# eco_Main_v1_0.net
KiCad netlist of a schematic drawn in Altium Designer
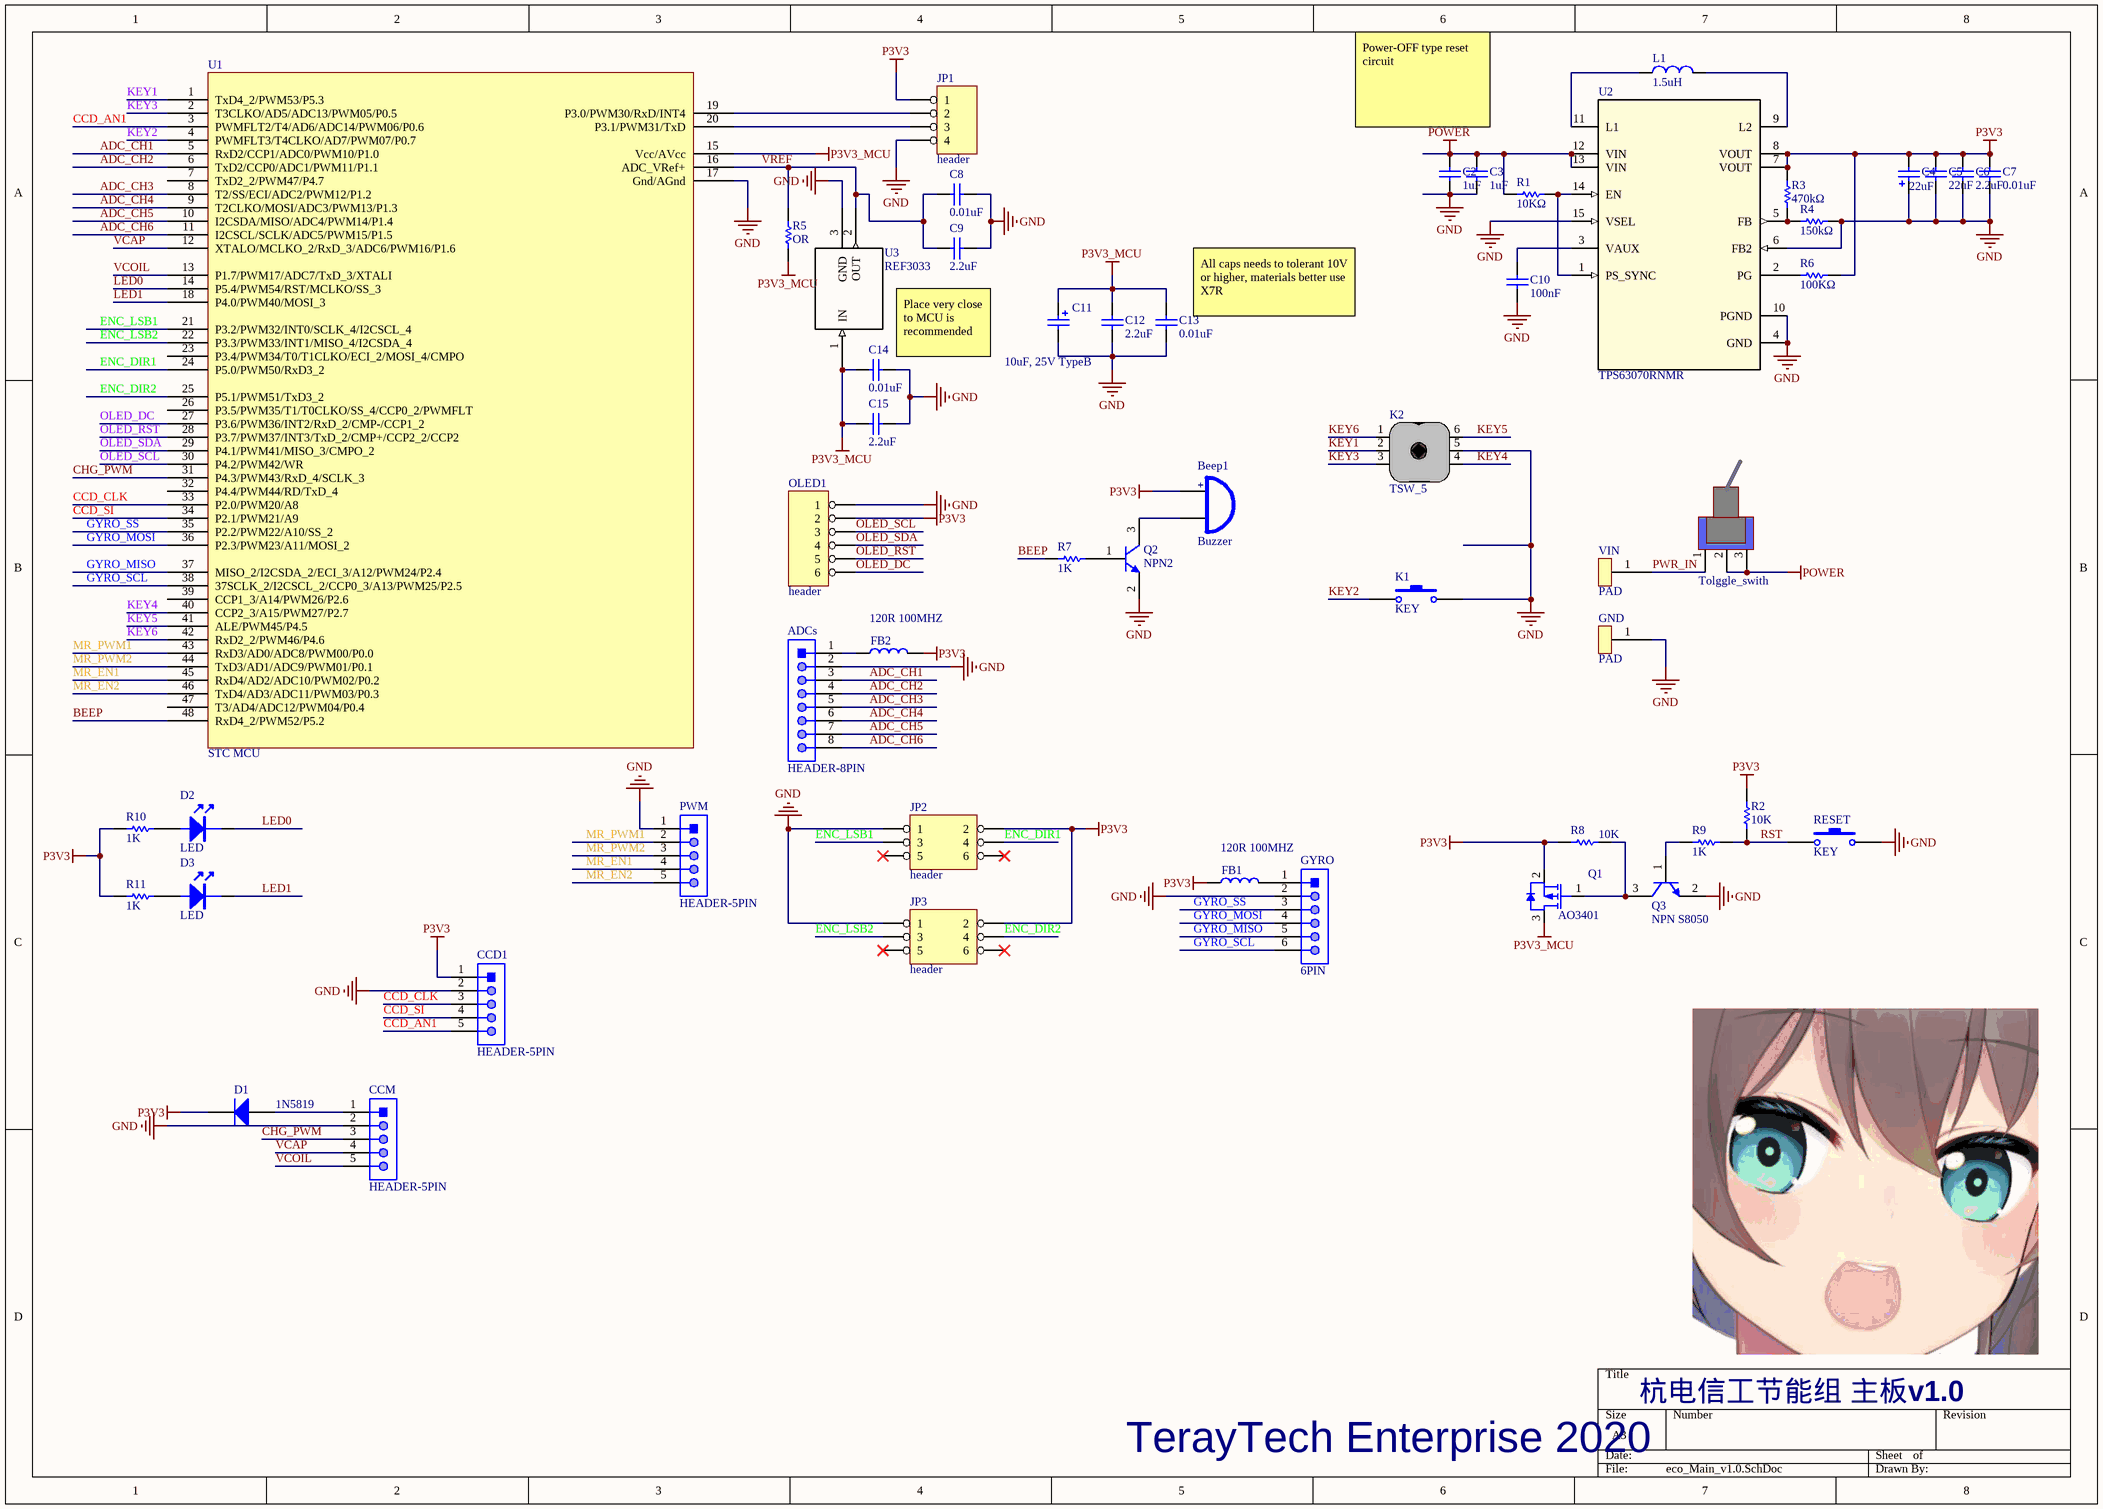
[diagram p0: eco_Main_v1.0.SchDoc]

(export (version "E")
  (design (tool "Eeschema 10.0.6"))
  (components
    (comp (ref "ADCs")
      (value "HEADER-8PIN")
      (footprint "HEADER_8P_1.25_RT")
      (libsource (lib "My Footprint") (part "HEADER-8PIN"))
    )
    (comp (ref "Beep1")
      (value "Buzzer")
      (footprint "BUZZER_9.6*9.6*5mm")
      (libsource (lib "My Footprint") (part "Buzzer"))
    )
    (comp (ref "C2")
      (value "1uF")
      (footprint "C1206")
      (description "Capacitor")
      (fields (field (name "PUBLISHER") "Altium Limited"))
      (libsource (lib "My Footprint") (part "CAP"))
    )
    (comp (ref "C3")
      (value "1uF")
      (footprint "0603_C")
      (description "Capacitor")
      (fields (field (name "PUBLISHER") "Altium Limited"))
      (libsource (lib "My Footprint") (part "CAP"))
    )
    (comp (ref "C4")
      (value "22uF")
      (footprint "CAPC3528B")
      (description "Capacitor")
      (fields (field (name "PUBLISHER") "Altium Limited"))
      (libsource (lib "My Footprint") (part "CAP_tan"))
    )
    (comp (ref "C5")
      (value "22uF")
      (footprint "C1206")
      (description "Capacitor")
      (fields (field (name "PUBLISHER") "Altium Limited"))
      (libsource (lib "My Footprint") (part "CAP"))
    )
    (comp (ref "C6")
      (value "2.2uF")
      (footprint "0603_C")
      (description "Capacitor")
      (fields (field (name "PUBLISHER") "Altium Limited"))
      (libsource (lib "My Footprint") (part "CAP"))
    )
    (comp (ref "C7")
      (value "0.01uF")
      (footprint "0603_C")
      (description "Capacitor")
      (fields (field (name "PUBLISHER") "Altium Limited"))
      (libsource (lib "My Footprint") (part "CAP"))
    )
    (comp (ref "C8")
      (value "0.01uF")
      (footprint "0603_C")
      (description "Capacitor")
      (fields (field (name "PUBLISHER") "Altium Limited"))
      (libsource (lib "My Footprint") (part "CAP"))
    )
    (comp (ref "C9")
      (value "2.2uF")
      (footprint "0603_C")
      (description "Capacitor")
      (fields (field (name "PUBLISHER") "Altium Limited"))
      (libsource (lib "My Footprint") (part "CAP"))
    )
    (comp (ref "C10")
      (value "100nF")
      (footprint "0603_C")
      (description "Capacitor")
      (fields (field (name "PUBLISHER") "Altium Limited"))
      (libsource (lib "My Footprint") (part "CAP"))
    )
    (comp (ref "C11")
      (value "10uF, 25V TypeB")
      (footprint "CAPC3528B")
      (description "Capacitor")
      (fields (field (name "PUBLISHER") "Altium Limited"))
      (libsource (lib "My Footprint") (part "CAP_tan"))
    )
    (comp (ref "C12")
      (value "2.2uF")
      (footprint "0603_C")
      (description "Capacitor")
      (fields (field (name "PUBLISHER") "Altium Limited"))
      (libsource (lib "My Footprint") (part "CAP"))
    )
    (comp (ref "C13")
      (value "0.01uF")
      (footprint "0603_C")
      (description "Capacitor")
      (fields (field (name "PUBLISHER") "Altium Limited"))
      (libsource (lib "My Footprint") (part "CAP"))
    )
    (comp (ref "C14")
      (value "0.01uF")
      (footprint "0603_C")
      (description "Capacitor")
      (fields (field (name "PUBLISHER") "Altium Limited"))
      (libsource (lib "My Footprint") (part "CAP"))
    )
    (comp (ref "C15")
      (value "2.2uF")
      (footprint "0603_C")
      (description "Capacitor")
      (fields (field (name "PUBLISHER") "Altium Limited"))
      (libsource (lib "My Footprint") (part "CAP"))
    )
    (comp (ref "CCD1")
      (value "HEADER-5PIN")
      (footprint "HEADER_5P_1.25_up")
      (libsource (lib "My Footprint") (part "HEADER-5PIN"))
    )
    (comp (ref "CCM")
      (value "HEADER-5PIN")
      (footprint "HEADER_5P_1.25_RT")
      (libsource (lib "My Footprint") (part "HEADER-5PIN"))
    )
    (comp (ref "D1")
      (value "1N5819")
      (footprint "SOD123")
      (description "40V 1A PEAK 25a")
      (libsource (lib "My Footprint") (part "1N5819"))
    )
    (comp (ref "D2")
      (value "LED")
      (footprint "0603_LED")
      (description "LED 发光二极管")
      (libsource (lib "My Footprint") (part "LED"))
    )
    (comp (ref "D3")
      (value "LED")
      (footprint "0603_LED")
      (description "LED 发光二极管")
      (libsource (lib "My Footprint") (part "LED"))
    )
    (comp (ref "Energy1")
      (value "Tolggle_swith")
      (footprint "TOGGLE SWICH STAND")
      (libsource (lib "SamacSys") (part "Tolggle_swith"))
    )
    (comp (ref "FB1")
      (value "120R 100MHZ")
      (footprint "FB0603")
      (description "120OHM@100MHZ 2A 25% 0603")
      (libsource (lib "My Footprint") (part "FB"))
    )
    (comp (ref "FB2")
      (value "120R 100MHZ")
      (footprint "FB0603")
      (description "120OHM@100MHZ 2A 25% 0603")
      (libsource (lib "My Footprint") (part "FB"))
    )
    (comp (ref "GND") (value "PAD") (footprint "PAD") (libsource (lib "My Footprint") (part "PAD")))
    (comp (ref "GYRO")
      (value "6PIN")
      (footprint "MX 1.25-WS-6P")
      (libsource (lib "My Footprint") (part "HEADER-6PIN"))
    )
    (comp (ref "JP1")
      (value "header")
      (footprint "header4")
      (libsource (lib "My Footprint") (part "HEADER 4"))
    )
    (comp (ref "JP2")
      (value "header")
      (footprint "header2X3")
      (libsource (lib "My Footprint") (part "HEADER 3X2"))
    )
    (comp (ref "JP3")
      (value "header")
      (footprint "header2X3")
      (libsource (lib "My Footprint") (part "HEADER 3X2"))
    )
    (comp (ref "K1")
      (value "KEY")
      (footprint "贴片复位开关")
      (description "Switch")
      (fields (field (name "PUBLISHER") "Altium Limited"))
      (libsource (lib "My Footprint") (part "KEY_2"))
    )
    (comp (ref "K2")
      (value "TSW_5")
      (footprint "TSW-10")
      (description "方向开关")
      (libsource (lib "My Footprint") (part "TSW_5"))
    )
    (comp (ref "L1") (value "1.5uH") (footprint "L 5x5") (libsource (lib "My Footprint") (part "Inductor")))
    (comp (ref "OLED1")
      (value "header")
      (footprint "0.96寸OLED模块")
      (libsource (lib "My Footprint") (part "HEADER 6"))
    )
    (comp (ref "PWM")
      (value "HEADER-5PIN")
      (footprint "HEADER_5P_1.25_RT")
      (libsource (lib "My Footprint") (part "HEADER-5PIN"))
    )
    (comp (ref "Q1")
      (value "AO3401")
      (footprint "SOT-23-3")
      (libsource (lib "SamacSys") (part "p-MOSEFT_SMALL"))
    )
    (comp (ref "Q2")
      (value "NPN2")
      (footprint "SOT-23-3")
      (description "贴片")
      (libsource (lib "My Footprint") (part "NPN2"))
    )
    (comp (ref "Q3")
      (value "NPN S8050")
      (footprint "SOT-23-3")
      (description "贴片")
      (libsource (lib "My Footprint") (part "NPN2"))
    )
    (comp (ref "R1")
      (value "10KΩ")
      (footprint "0603_R")
      (description "Resistor")
      (fields (field (name "PUBLISHER") "Altium Limited"))
      (libsource (lib "My Footprint") (part "RES0"))
    )
    (comp (ref "R2")
      (value "10K")
      (footprint "0603_R")
      (description "Resistor")
      (fields (field (name "PUBLISHER") "Altium Limited"))
      (libsource (lib "My Footprint") (part "RES0"))
    )
    (comp (ref "R3")
      (value "470kΩ")
      (footprint "0603_R")
      (description "Resistor")
      (fields (field (name "PUBLISHER") "Altium Limited"))
      (libsource (lib "My Footprint") (part "RES0"))
    )
    (comp (ref "R4")
      (value "150kΩ")
      (footprint "0603_R")
      (description "Resistor")
      (fields (field (name "PUBLISHER") "Altium Limited"))
      (libsource (lib "My Footprint") (part "RES0"))
    )
    (comp (ref "R5")
      (value "OR")
      (footprint "0603_R")
      (description "Resistor")
      (fields (field (name "PUBLISHER") "Altium Limited"))
      (libsource (lib "My Footprint") (part "RES0"))
    )
    (comp (ref "R6")
      (value "100KΩ")
      (footprint "0603_R")
      (description "Resistor")
      (fields (field (name "PUBLISHER") "Altium Limited"))
      (libsource (lib "My Footprint") (part "RES0"))
    )
    (comp (ref "R7")
      (value "1K")
      (footprint "0603_R")
      (description "Resistor")
      (fields (field (name "PUBLISHER") "Altium Limited"))
      (libsource (lib "My Footprint") (part "RES"))
    )
    (comp (ref "R8")
      (value "10K")
      (footprint "0603_R")
      (description "Resistor")
      (fields (field (name "PUBLISHER") "Altium Limited"))
      (libsource (lib "My Footprint") (part "RES0"))
    )
    (comp (ref "R9")
      (value "1K")
      (footprint "0603_R")
      (description "Resistor")
      (fields (field (name "PUBLISHER") "Altium Limited"))
      (libsource (lib "My Footprint") (part "RES0"))
    )
    (comp (ref "R10")
      (value "1K")
      (footprint "0603_R")
      (description "Resistor")
      (fields (field (name "PUBLISHER") "Altium Limited"))
      (libsource (lib "My Footprint") (part "RES0"))
    )
    (comp (ref "R11")
      (value "1K")
      (footprint "0603_R")
      (description "Resistor")
      (fields (field (name "PUBLISHER") "Altium Limited"))
      (libsource (lib "My Footprint") (part "RES0"))
    )
    (comp (ref "RESET")
      (value "KEY")
      (footprint "KEY_2")
      (description "Switch")
      (fields (field (name "PUBLISHER") "Altium Limited"))
      (libsource (lib "My Footprint") (part "KEY_2"))
    )
    (comp (ref "U1") (value "STC MCU") (footprint "LQFP48") (libsource (lib "SamacSys") (part "STC8G2K64S4")))
    (comp (ref "U2")
      (value "TPS63070RNMR")
      (footprint "RNM0015A")
      (description "Imported")
      (fields (field (name "MANUFACTURER") "Texas Instruments"))
      (libsource (lib "SamacSys") (part "TPS63070RNMR"))
    )
    (comp (ref "U3")
      (value "REF3033")
      (footprint "DBZ3")
      (description "Imported")
      (fields
        (field (name "MANUFACTURER") "Texas Instruments")
        (field (name "MANUFACTURER_PART_NUMBER") "ref3033_dbz_3")
      )
      (libsource (lib "My Footprint") (part "REF3033_DBZ_3"))
    )
    (comp (ref "VIN") (value "PAD") (footprint "PAD") (libsource (lib "My Footprint") (part "PAD")))
  )
  (nets
    (net (code "1") (name "/ADC_CH1") (class "Default")
      (node (ref "ADCs") (pin "3") (pinfunction "3_3") (pintype "passive"))
      (node (ref "U1") (pin "5") (pinfunction "RxD2/CCP1/ADC0/PWM10/P1.0_5") (pintype "passive"))
    )
    (net (code "2") (name "/ADC_CH2") (class "Default")
      (node (ref "ADCs") (pin "4") (pinfunction "4_4") (pintype "passive"))
      (node (ref "U1") (pin "6") (pinfunction "TxD2/CCP0/ADC1/PWM11/P1.1_6") (pintype "passive"))
    )
    (net (code "3") (name "/ADC_CH3") (class "Default")
      (node (ref "ADCs") (pin "5") (pinfunction "5_5") (pintype "passive"))
      (node (ref "U1") (pin "8") (pinfunction "T2/SS/ECI/ADC2/PWM12/P1.2_8") (pintype "passive"))
    )
    (net (code "4") (name "/ADC_CH4") (class "Default")
      (node (ref "ADCs") (pin "6") (pinfunction "6_6") (pintype "passive"))
      (node (ref "U1") (pin "9") (pinfunction "T2CLKO/MOSI/ADC3/PWM13/P1.3_9") (pintype "passive"))
    )
    (net (code "5") (name "/ADC_CH5") (class "Default")
      (node (ref "ADCs") (pin "7") (pinfunction "7_7") (pintype "passive"))
      (node (ref "U1") (pin "10") (pinfunction "I2CSDA/MISO/ADC4/PWM14/P1.4_10") (pintype "passive"))
    )
    (net (code "6") (name "/ADC_CH6") (class "Default")
      (node (ref "ADCs") (pin "8") (pinfunction "8_8") (pintype "passive"))
      (node (ref "U1") (pin "11") (pinfunction "I2CSCL/SCLK/ADC5/PWM15/P1.5_11") (pintype "passive"))
    )
    (net (code "7") (name "/BEEP") (class "Default")
      (node (ref "R7") (pin "1") (pinfunction "1_1") (pintype "passive"))
      (node (ref "U1") (pin "48") (pinfunction "RxD4_2/PWM52/P5.2_48") (pintype "passive"))
    )
    (net (code "8") (name "/CCD_AN1") (class "Default")
      (node (ref "CCD1") (pin "5") (pinfunction "5_5") (pintype "passive"))
      (node (ref "U1") (pin "3") (pinfunction "PWMFLT2/T4/AD6/ADC14/PWM06/P0.6_3") (pintype "passive"))
    )
    (net (code "9") (name "/CCD_CLK") (class "Default")
      (node (ref "CCD1") (pin "3") (pinfunction "3_3") (pintype "passive"))
      (node (ref "U1") (pin "33") (pinfunction "P2.0/PWM20/A8_33") (pintype "passive"))
    )
    (net (code "10") (name "/CCD_SI") (class "Default")
      (node (ref "CCD1") (pin "4") (pinfunction "4_4") (pintype "passive"))
      (node (ref "U1") (pin "34") (pinfunction "P2.1/PWM21/A9_34") (pintype "passive"))
    )
    (net (code "11") (name "/CHG_PWM") (class "Default")
      (node (ref "CCM") (pin "3") (pinfunction "3_3") (pintype "passive"))
      (node (ref "U1") (pin "31") (pinfunction "P4.3/PWM43/RxD_4/SCLK_3_31") (pintype "passive"))
    )
    (net (code "12") (name "/ENC_DIR1") (class "Default")
      (node (ref "JP2") (pin "4") (pinfunction "4_4") (pintype "passive"))
      (node (ref "U1") (pin "24") (pinfunction "P5.0/PWM50/RxD3_2_24") (pintype "passive"))
    )
    (net (code "13") (name "/ENC_DIR2") (class "Default")
      (node (ref "JP3") (pin "4") (pinfunction "4_4") (pintype "passive"))
      (node (ref "U1") (pin "25") (pinfunction "P5.1/PWM51/TxD3_2_25") (pintype "passive"))
    )
    (net (code "14") (name "/ENC_LSB1") (class "Default")
      (node (ref "JP2") (pin "3") (pinfunction "3_3") (pintype "passive"))
      (node (ref "U1") (pin "21") (pinfunction "P3.2/PWM32/INT0/SCLK_4/I2CSCL_4_21") (pintype "passive"))
    )
    (net (code "15") (name "/ENC_LSB2") (class "Default")
      (node (ref "JP3") (pin "3") (pinfunction "3_3") (pintype "passive"))
      (node (ref "U1") (pin "22") (pinfunction "P3.3/PWM33/INT1/MISO_4/I2CSDA_4_22") (pintype "passive"))
    )
    (net (code "16") (name "/GYRO_MISO") (class "Default")
      (node (ref "GYRO") (pin "5") (pinfunction "5_5") (pintype "passive"))
      (node (ref "U1") (pin "37") (pinfunction "MISO_2/I2CSDA_2/ECI_3/A12/PWM24/P2.4_37") (pintype "passive"))
    )
    (net (code "17") (name "/GYRO_MOSI") (class "Default")
      (node (ref "GYRO") (pin "4") (pinfunction "4_4") (pintype "passive"))
      (node (ref "U1") (pin "36") (pinfunction "P2.3/PWM23/A11/MOSI_2_36") (pintype "passive"))
    )
    (net (code "18") (name "/GYRO_SCL") (class "Default")
      (node (ref "GYRO") (pin "6") (pinfunction "6_6") (pintype "passive"))
      (node (ref "U1") (pin "38") (pinfunction "37SCLK_2/I2CSCL_2/CCP0_3/A13/PWM25/P2.5_38") (pintype "passive"))
    )
    (net (code "19") (name "/GYRO_SS") (class "Default")
      (node (ref "GYRO") (pin "3") (pinfunction "3_3") (pintype "passive"))
      (node (ref "U1") (pin "35") (pinfunction "P2.2/PWM22/A10/SS_2_35") (pintype "passive"))
    )
    (net (code "20") (name "/KEY1") (class "Default")
      (node (ref "K2") (pin "2") (pintype "passive"))
      (node (ref "U1") (pin "1") (pinfunction "TxD4_2/PWM53/P5.3_1") (pintype "passive"))
    )
    (net (code "21") (name "/KEY2") (class "Default")
      (node (ref "K1") (pin "1") (pinfunction "1_1") (pintype "passive"))
      (node (ref "U1") (pin "4") (pinfunction "PWMFLT3/T4CLKO/AD7/PWM07/P0.7_4") (pintype "passive"))
    )
    (net (code "22") (name "/KEY3") (class "Default")
      (node (ref "K2") (pin "3") (pintype "passive"))
      (node (ref "U1") (pin "2") (pinfunction "T3CLKO/AD5/ADC13/PWM05/P0.5_2") (pintype "passive"))
    )
    (net (code "23") (name "/KEY4") (class "Default")
      (node (ref "K2") (pin "4") (pintype "passive"))
      (node (ref "U1") (pin "40") (pinfunction "CCP2_3/A15/PWM27/P2.7_40") (pintype "passive"))
    )
    (net (code "24") (name "/KEY5") (class "Default")
      (node (ref "K2") (pin "6") (pintype "passive"))
      (node (ref "U1") (pin "41") (pinfunction "ALE/PWM45/P4.5_41") (pintype "passive"))
    )
    (net (code "25") (name "/KEY6") (class "Default")
      (node (ref "K2") (pin "1") (pintype "passive"))
      (node (ref "U1") (pin "42") (pinfunction "RxD2_2/PWM46/P4.6_42") (pintype "passive"))
    )
    (net (code "26") (name "/LED0") (class "Default")
      (node (ref "D2") (pin "2") (pinfunction "K_2") (pintype "passive"))
      (node (ref "U1") (pin "14") (pinfunction "P5.4/PWM54/RST/MCLKO/SS_3_14") (pintype "passive"))
    )
    (net (code "27") (name "/LED1") (class "Default")
      (node (ref "D3") (pin "2") (pinfunction "K_2") (pintype "passive"))
      (node (ref "U1") (pin "18") (pinfunction "P4.0/PWM40/MOSI_3_18") (pintype "passive"))
    )
    (net (code "28") (name "/MR_EN1") (class "Default")
      (node (ref "PWM") (pin "4") (pinfunction "4_4") (pintype "passive"))
      (node (ref "U1") (pin "45") (pinfunction "RxD4/AD2/ADC10/PWM02/P0.2_45") (pintype "passive"))
    )
    (net (code "29") (name "/MR_EN2") (class "Default")
      (node (ref "PWM") (pin "5") (pinfunction "5_5") (pintype "passive"))
      (node (ref "U1") (pin "46") (pinfunction "TxD4/AD3/ADC11/PWM03/P0.3_46") (pintype "passive"))
    )
    (net (code "30") (name "/MR_PWM1") (class "Default")
      (node (ref "PWM") (pin "2") (pinfunction "2_2") (pintype "passive"))
      (node (ref "U1") (pin "43") (pinfunction "RxD3/AD0/ADC8/PWM00/P0.0_43") (pintype "passive"))
    )
    (net (code "31") (name "/MR_PWM2") (class "Default")
      (node (ref "PWM") (pin "3") (pinfunction "3_3") (pintype "passive"))
      (node (ref "U1") (pin "44") (pinfunction "TxD3/AD1/ADC9/PWM01/P0.1_44") (pintype "passive"))
    )
    (net (code "32") (name "/OLED_DC") (class "Default")
      (node (ref "OLED1") (pin "6") (pinfunction "6_6") (pintype "passive"))
      (node (ref "U1") (pin "27") (pinfunction "P3.6/PWM36/INT2/RxD_2/CMP-/CCP1_2_27") (pintype "passive"))
    )
    (net (code "33") (name "/OLED_RST") (class "Default")
      (node (ref "OLED1") (pin "5") (pinfunction "5_5") (pintype "passive"))
      (node (ref "U1") (pin "28") (pinfunction "P3.7/PWM37/INT3/TxD_2/CMP+/CCP2_2/CCP2_28") (pintype "passive"))
    )
    (net (code "34") (name "/OLED_SCL") (class "Default")
      (node (ref "OLED1") (pin "3") (pinfunction "3_3") (pintype "passive"))
      (node (ref "U1") (pin "30") (pinfunction "P4.2/PWM42/WR_30") (pintype "passive"))
    )
    (net (code "35") (name "/OLED_SDA") (class "Default")
      (node (ref "OLED1") (pin "4") (pinfunction "4_4") (pintype "passive"))
      (node (ref "U1") (pin "29") (pinfunction "P4.1/PWM41/MISO_3/CMPO_2_29") (pintype "passive"))
    )
    (net (code "36") (name "/PWR_IN") (class "Default")
      (node (ref "Energy1") (pin "1") (pintype "passive"))
      (node (ref "VIN") (pin "1") (pintype "passive"))
    )
    (net (code "37") (name "/RST") (class "Default")
      (node (ref "R2") (pin "2") (pinfunction "2_2") (pintype "passive"))
      (node (ref "R9") (pin "2") (pinfunction "2_2") (pintype "passive"))
      (node (ref "RESET") (pin "1") (pinfunction "1_1") (pintype "passive"))
    )
    (net (code "38") (name "/VCAP") (class "Default")
      (node (ref "CCM") (pin "4") (pinfunction "4_4") (pintype "passive"))
      (node (ref "U1") (pin "12") (pinfunction "XTALO/MCLKO_2/RxD_3/ADC6/PWM16/P1.6_12") (pintype "passive"))
    )
    (net (code "39") (name "/VCOIL") (class "Default")
      (node (ref "CCM") (pin "5") (pinfunction "5_5") (pintype "passive"))
      (node (ref "U1") (pin "13") (pinfunction "P1.7/PWM17/ADC7/TxD_3/XTALI_13") (pintype "passive"))
    )
    (net (code "40") (name "/VREF") (class "Default")
      (node (ref "C8") (pin "1") (pinfunction "1_1") (pintype "passive"))
      (node (ref "C9") (pin "1") (pinfunction "1_1") (pintype "passive"))
      (node (ref "R5") (pin "1") (pinfunction "1_1") (pintype "passive"))
      (node (ref "U1") (pin "16") (pinfunction "ADC_VRef+_16") (pintype "passive"))
      (node (ref "U3") (pin "2") (pinfunction "OUT_2") (pintype "output"))
    )
    (net (code "41") (name "GND") (class "Default")
      (node (ref "ADCs") (pin "2") (pinfunction "2_2") (pintype "passive"))
      (node (ref "C10") (pin "1") (pinfunction "1_1") (pintype "passive"))
      (node (ref "C11") (pin "2") (pinfunction "2_2") (pintype "passive"))
      (node (ref "C12") (pin "1") (pinfunction "1_1") (pintype "passive"))
      (node (ref "C13") (pin "1") (pinfunction "1_1") (pintype "passive"))
      (node (ref "C14") (pin "2") (pinfunction "2_2") (pintype "passive"))
      (node (ref "C15") (pin "2") (pinfunction "2_2") (pintype "passive"))
      (node (ref "C2") (pin "1") (pinfunction "1_1") (pintype "passive"))
      (node (ref "C3") (pin "1") (pinfunction "1_1") (pintype "passive"))
      (node (ref "C4") (pin "1") (pinfunction "1_1") (pintype "passive"))
      (node (ref "C5") (pin "1") (pinfunction "1_1") (pintype "passive"))
      (node (ref "C6") (pin "1") (pinfunction "1_1") (pintype "passive"))
      (node (ref "C7") (pin "1") (pinfunction "1_1") (pintype "passive"))
      (node (ref "C8") (pin "2") (pinfunction "2_2") (pintype "passive"))
      (node (ref "C9") (pin "2") (pinfunction "2_2") (pintype "passive"))
      (node (ref "CCD1") (pin "2") (pinfunction "2_2") (pintype "passive"))
      (node (ref "CCM") (pin "2") (pinfunction "2_2") (pintype "passive"))
      (node (ref "GND") (pin "1") (pintype "passive"))
      (node (ref "GYRO") (pin "2") (pinfunction "2_2") (pintype "passive"))
      (node (ref "JP1") (pin "4") (pinfunction "4_4") (pintype "passive"))
      (node (ref "JP2") (pin "1") (pinfunction "1_1") (pintype "passive"))
      (node (ref "JP3") (pin "1") (pinfunction "1_1") (pintype "passive"))
      (node (ref "K1") (pin "2") (pinfunction "2_2") (pintype "passive"))
      (node (ref "K2") (pin "5") (pintype "passive"))
      (node (ref "OLED1") (pin "1") (pinfunction "1_1") (pintype "passive"))
      (node (ref "PWM") (pin "1") (pinfunction "1_1") (pintype "passive"))
      (node (ref "Q2") (pin "2") (pinfunction "E_2") (pintype "passive"))
      (node (ref "Q3") (pin "2") (pinfunction "E_2") (pintype "passive"))
      (node (ref "R4") (pin "1") (pinfunction "1_1") (pintype "passive"))
      (node (ref "RESET") (pin "2") (pinfunction "2_2") (pintype "passive"))
      (node (ref "U1") (pin "17") (pinfunction "Gnd/AGnd_17") (pintype "passive"))
      (node (ref "U2") (pin "10") (pinfunction "PGND_10") (pintype "power_in"))
      (node (ref "U2") (pin "15") (pinfunction "VSEL_15") (pintype "input"))
      (node (ref "U2") (pin "4") (pinfunction "GND_4") (pintype "power_in"))
      (node (ref "U2") (pin "6") (pinfunction "FB2_6") (pintype "input"))
      (node (ref "U3") (pin "3") (pinfunction "GND_3") (pintype "power_in"))
    )
    (net (code "42") (name "Net-(ADCs-Pad1)") (class "Default")
      (node (ref "ADCs") (pin "1") (pinfunction "1_1") (pintype "passive"))
      (node (ref "FB2") (pin "1") (pinfunction "1_1") (pintype "passive"))
    )
    (net (code "43") (name "Net-(Beep1-B)") (class "Default")
      (node (ref "Beep1") (pin "2") (pinfunction "B_2") (pintype "passive"))
      (node (ref "Q2") (pin "3") (pinfunction "C_3") (pintype "passive"))
    )
    (net (code "44") (name "Net-(D1-A)") (class "Default")
      (node (ref "CCM") (pin "1") (pinfunction "1_1") (pintype "passive"))
      (node (ref "D1") (pin "1") (pinfunction "A_1") (pintype "passive"))
    )
    (net (code "45") (name "Net-(D2-A)") (class "Default")
      (node (ref "D2") (pin "1") (pinfunction "A_1") (pintype "passive"))
      (node (ref "R10") (pin "2") (pinfunction "2_2") (pintype "passive"))
    )
    (net (code "46") (name "Net-(D3-A)") (class "Default")
      (node (ref "D3") (pin "1") (pinfunction "A_1") (pintype "passive"))
      (node (ref "R11") (pin "2") (pinfunction "2_2") (pintype "passive"))
    )
    (net (code "47") (name "Net-(FB1-Pad2)") (class "Default")
      (node (ref "FB1") (pin "2") (pinfunction "2_2") (pintype "passive"))
      (node (ref "GYRO") (pin "1") (pinfunction "1_1") (pintype "passive"))
    )
    (net (code "48") (name "Net-(Q1-G)") (class "Default")
      (node (ref "Q1") (pin "1") (pinfunction "G_1") (pintype "passive"))
      (node (ref "Q3") (pin "3") (pinfunction "C_3") (pintype "passive"))
      (node (ref "R8") (pin "1") (pinfunction "1_1") (pintype "passive"))
    )
    (net (code "49") (name "Net-(Q2-B)") (class "Default")
      (node (ref "Q2") (pin "1") (pinfunction "B_1") (pintype "passive"))
      (node (ref "R7") (pin "2") (pinfunction "2_2") (pintype "passive"))
    )
    (net (code "50") (name "Net-(Q3-B)") (class "Default")
      (node (ref "Q3") (pin "1") (pinfunction "B_1") (pintype "passive"))
      (node (ref "R9") (pin "1") (pinfunction "1_1") (pintype "passive"))
    )
    (net (code "51") (name "Net-(U1-P3.0{slash}PWM30{slash}RxD{slash}INT4)") (class "Default")
      (node (ref "JP1") (pin "2") (pinfunction "2_2") (pintype "passive"))
      (node (ref "U1") (pin "19") (pinfunction "P3.0/PWM30/RxD/INT4_19") (pintype "passive"))
    )
    (net (code "52") (name "Net-(U1-P3.1{slash}PWM31{slash}TxD)") (class "Default")
      (node (ref "JP1") (pin "3") (pinfunction "3_3") (pintype "passive"))
      (node (ref "U1") (pin "20") (pinfunction "P3.1/PWM31/TxD_20") (pintype "passive"))
    )
    (net (code "53") (name "Net-(U2-EN)") (class "Default")
      (node (ref "R1") (pin "1") (pinfunction "1_1") (pintype "passive"))
      (node (ref "U2") (pin "1") (pinfunction "PS_SYNC_1") (pintype "input"))
      (node (ref "U2") (pin "14") (pinfunction "EN_14") (pintype "input"))
    )
    (net (code "54") (name "Net-(U2-FB)") (class "Default")
      (node (ref "R3") (pin "1") (pinfunction "1_1") (pintype "passive"))
      (node (ref "R4") (pin "2") (pinfunction "2_2") (pintype "passive"))
      (node (ref "U2") (pin "5") (pinfunction "FB_5") (pintype "output"))
    )
    (net (code "55") (name "Net-(U2-L1)") (class "Default")
      (node (ref "L1") (pin "1") (pinfunction "1_1") (pintype "passive"))
      (node (ref "U2") (pin "11") (pinfunction "L1_11") (pintype "passive"))
    )
    (net (code "56") (name "Net-(U2-L2)") (class "Default")
      (node (ref "L1") (pin "2") (pinfunction "2_2") (pintype "passive"))
      (node (ref "U2") (pin "9") (pinfunction "L2_9") (pintype "passive"))
    )
    (net (code "57") (name "Net-(U2-PG)") (class "Default")
      (node (ref "R6") (pin "2") (pinfunction "2_2") (pintype "passive"))
      (node (ref "U2") (pin "2") (pinfunction "PG_2") (pintype "open_collector"))
    )
    (net (code "58") (name "Net-(U2-VAUX)") (class "Default")
      (node (ref "C10") (pin "2") (pinfunction "2_2") (pintype "passive"))
      (node (ref "U2") (pin "3") (pinfunction "VAUX_3") (pintype "passive"))
    )
    (net (code "59") (name "P3V3") (class "Default")
      (node (ref "Beep1") (pin "1") (pinfunction "A_1") (pintype "passive"))
      (node (ref "C4") (pin "2") (pinfunction "2_2") (pintype "passive"))
      (node (ref "C5") (pin "2") (pinfunction "2_2") (pintype "passive"))
      (node (ref "C6") (pin "2") (pinfunction "2_2") (pintype "passive"))
      (node (ref "C7") (pin "2") (pinfunction "2_2") (pintype "passive"))
      (node (ref "CCD1") (pin "1") (pinfunction "1_1") (pintype "passive"))
      (node (ref "D1") (pin "2") (pinfunction "K_2") (pintype "passive"))
      (node (ref "FB1") (pin "1") (pinfunction "1_1") (pintype "passive"))
      (node (ref "FB2") (pin "2") (pinfunction "2_2") (pintype "passive"))
      (node (ref "JP1") (pin "1") (pinfunction "1_1") (pintype "passive"))
      (node (ref "JP2") (pin "2") (pinfunction "2_2") (pintype "passive"))
      (node (ref "JP3") (pin "2") (pinfunction "2_2") (pintype "passive"))
      (node (ref "OLED1") (pin "2") (pinfunction "2_2") (pintype "passive"))
      (node (ref "Q1") (pin "2") (pinfunction "S_2") (pintype "passive"))
      (node (ref "R10") (pin "1") (pinfunction "1_1") (pintype "passive"))
      (node (ref "R11") (pin "1") (pinfunction "1_1") (pintype "passive"))
      (node (ref "R2") (pin "1") (pinfunction "1_1") (pintype "passive"))
      (node (ref "R3") (pin "2") (pinfunction "2_2") (pintype "passive"))
      (node (ref "R6") (pin "1") (pinfunction "1_1") (pintype "passive"))
      (node (ref "R8") (pin "2") (pinfunction "2_2") (pintype "passive"))
      (node (ref "U2") (pin "7") (pinfunction "VOUT_7") (pintype "power_in"))
      (node (ref "U2") (pin "8") (pinfunction "VOUT_8") (pintype "power_in"))
    )
    (net (code "60") (name "P3V3_MCU") (class "Default")
      (node (ref "C11") (pin "1") (pinfunction "1_1") (pintype "passive"))
      (node (ref "C12") (pin "2") (pinfunction "2_2") (pintype "passive"))
      (node (ref "C13") (pin "2") (pinfunction "2_2") (pintype "passive"))
      (node (ref "C14") (pin "1") (pinfunction "1_1") (pintype "passive"))
      (node (ref "C15") (pin "1") (pinfunction "1_1") (pintype "passive"))
      (node (ref "Q1") (pin "3") (pinfunction "D_3") (pintype "passive"))
      (node (ref "R5") (pin "2") (pinfunction "2_2") (pintype "passive"))
      (node (ref "U1") (pin "15") (pinfunction "Vcc/AVcc_15") (pintype "passive"))
      (node (ref "U3") (pin "1") (pinfunction "IN_1") (pintype "input"))
    )
    (net (code "61") (name "POWER") (class "Default")
      (node (ref "C2") (pin "2") (pinfunction "2_2") (pintype "passive"))
      (node (ref "C3") (pin "2") (pinfunction "2_2") (pintype "passive"))
      (node (ref "Energy1") (pin "2") (pintype "passive"))
      (node (ref "Energy1") (pin "3") (pintype "passive"))
      (node (ref "R1") (pin "2") (pinfunction "2_2") (pintype "passive"))
      (node (ref "U2") (pin "12") (pinfunction "VIN_12") (pintype "power_in"))
      (node (ref "U2") (pin "13") (pinfunction "VIN_13") (pintype "power_in"))
    )
    (net (code "62") (name "unconnected-(JP2-Pad5)") (class "Default")
      (node (ref "JP2") (pin "5") (pinfunction "5_5") (pintype "passive+no_connect"))
    )
    (net (code "63") (name "unconnected-(JP2-Pad6)") (class "Default")
      (node (ref "JP2") (pin "6") (pinfunction "6_6") (pintype "passive+no_connect"))
    )
    (net (code "64") (name "unconnected-(JP3-Pad5)") (class "Default")
      (node (ref "JP3") (pin "5") (pinfunction "5_5") (pintype "passive+no_connect"))
    )
    (net (code "65") (name "unconnected-(JP3-Pad6)") (class "Default")
      (node (ref "JP3") (pin "6") (pinfunction "6_6") (pintype "passive+no_connect"))
    )
    (net (code "66") (name "unconnected-(U1-CCP1_3{slash}A14{slash}PWM26{slash}P2.6-Pad39)") (class "Default")
      (node (ref "U1") (pin "39") (pinfunction "CCP1_3/A14/PWM26/P2.6_39") (pintype "passive"))
    )
    (net (code "67") (name "unconnected-(U1-P3.4{slash}PWM34{slash}T0{slash}T1CLKO{slash}ECI_2{slash}MOSI_4{slash}CMPO-Pad23)") (class "Default")
      (node (ref "U1") (pin "23") (pinfunction "P3.4/PWM34/T0/T1CLKO/ECI_2/MOSI_4/CMPO_23") (pintype "passive"))
    )
    (net (code "68") (name "unconnected-(U1-P3.5{slash}PWM35{slash}T1{slash}T0CLKO{slash}SS_4{slash}CCP0_2{slash}PWMFLT-Pad26)") (class "Default")
      (node (ref "U1") (pin "26") (pinfunction "P3.5/PWM35/T1/T0CLKO/SS_4/CCP0_2/PWMFLT_26") (pintype "passive"))
    )
    (net (code "69") (name "unconnected-(U1-P4.4{slash}PWM44{slash}RD{slash}TxD_4-Pad32)") (class "Default")
      (node (ref "U1") (pin "32") (pinfunction "P4.4/PWM44/RD/TxD_4_32") (pintype "passive"))
    )
    (net (code "70") (name "unconnected-(U1-T3{slash}AD4{slash}ADC12{slash}PWM04{slash}P0.4-Pad47)") (class "Default")
      (node (ref "U1") (pin "47") (pinfunction "T3/AD4/ADC12/PWM04/P0.4_47") (pintype "passive"))
    )
    (net (code "71") (name "unconnected-(U1-TxD2_2{slash}PWM47{slash}P4.7-Pad7)") (class "Default")
      (node (ref "U1") (pin "7") (pinfunction "TxD2_2/PWM47/P4.7_7") (pintype "passive"))
    )
  )
)
